# 1-Schematic_PhotoMag.net
KiCad netlist of a schematic drawn in EasyEDA
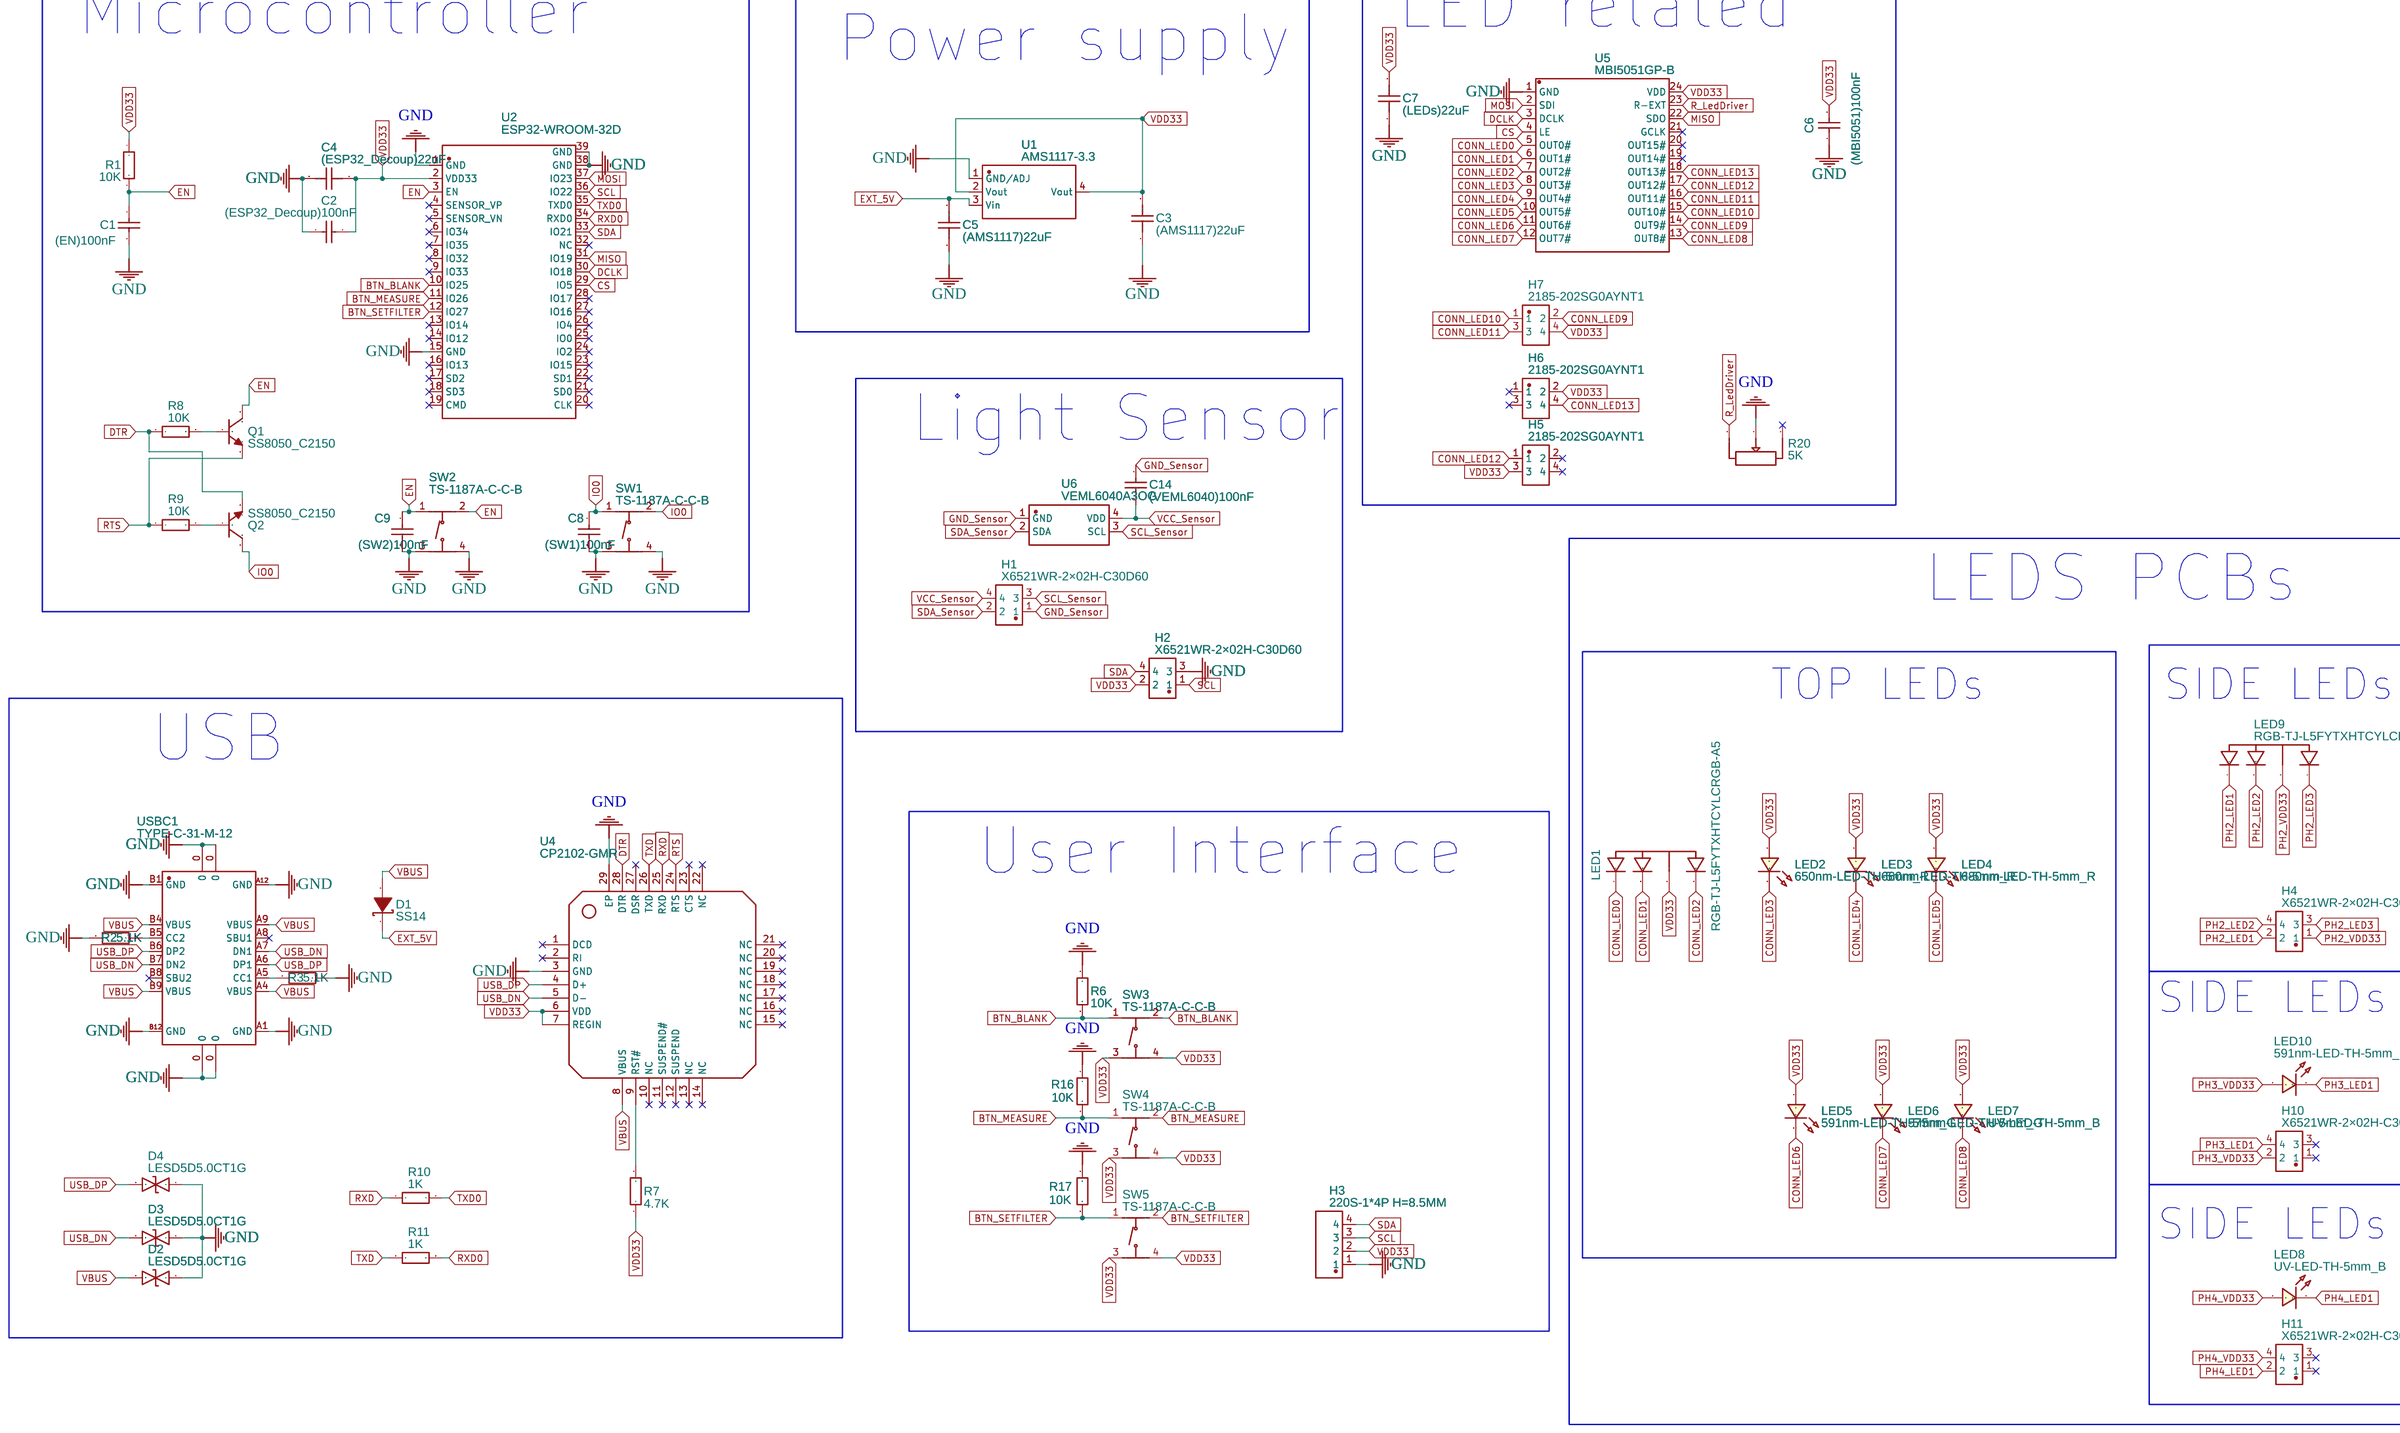
[diagram p0: schematic sheet]

(export (version "E")
  (design (tool "Eeschema 10.0.6"))
  (components
    (comp (ref "C1")
      (value "(EN)100nF")
      (fields
        (field (name "BOM_Manufacturer Part") "CL31B104KBCNNNC")
        (field (name "BOM_Supplier Part") "C24497")
      )
      (libsource (lib "") (part "CL31B104KBCNNNC_2"))
    )
    (comp (ref "C2")
      (value "(ESP32_Decoup)100nF")
      (fields
        (field (name "BOM_Manufacturer Part") "CL31B104KBCNNNC")
        (field (name "BOM_Supplier Part") "C24497")
      )
      (libsource (lib "") (part "CL31B104KBCNNNC_3"))
    )
    (comp (ref "C3")
      (value "(AMS1117)22uF")
      (fields
        (field (name "BOM_Manufacturer Part") "CL21A226MAQNNNE")
        (field (name "BOM_Supplier Part") "C45783")
      )
      (libsource (lib "") (part "CL21A226MAQNNNE"))
    )
    (comp (ref "C4")
      (value "(ESP32_Decoup)22uF")
      (fields
        (field (name "BOM_Manufacturer Part") "CL21A226MAQNNNE")
        (field (name "BOM_Supplier Part") "C45783")
      )
      (libsource (lib "") (part "CL21A226MAQNNNE_1"))
    )
    (comp (ref "C5")
      (value "(AMS1117)22uF")
      (fields
        (field (name "BOM_Manufacturer Part") "CL21A226MAQNNNE")
        (field (name "BOM_Supplier Part") "C45783")
      )
      (libsource (lib "") (part "CL21A226MAQNNNE"))
    )
    (comp (ref "C6")
      (value "(MBI5051)100nF")
      (fields
        (field (name "BOM_Manufacturer Part") "CL31B104KBCNNNC")
        (field (name "BOM_Supplier Part") "C24497")
      )
      (libsource (lib "") (part "CL31B104KBCNNNC_1"))
    )
    (comp (ref "C7")
      (value "(LEDs)22uF")
      (fields
        (field (name "BOM_Manufacturer Part") "CL21A226MAQNNNE")
        (field (name "BOM_Supplier Part") "C45783")
      )
      (libsource (lib "") (part "CL21A226MAQNNNE"))
    )
    (comp (ref "C8")
      (value "(SW1)100nF")
      (fields
        (field (name "BOM_Manufacturer Part") "CL31B104KBCNNNC")
        (field (name "BOM_Supplier Part") "C24497")
      )
      (libsource (lib "") (part "CL31B104KBCNNNC"))
    )
    (comp (ref "C9")
      (value "(SW2)100nF")
      (fields
        (field (name "BOM_Manufacturer Part") "CL31B104KBCNNNC")
        (field (name "BOM_Supplier Part") "C24497")
      )
      (libsource (lib "") (part "CL31B104KBCNNNC"))
    )
    (comp (ref "C14")
      (value "(VEML6040)100nF")
      (fields
        (field (name "BOM_Manufacturer Part") "CL31B104KBCNNNC")
        (field (name "BOM_Supplier Part") "C24497")
      )
      (libsource (lib "") (part "CL31B104KBCNNNC_4"))
    )
    (comp (ref "D1")
      (value "SS14")
      (fields (field (name "BOM_Supplier Part") "C2480"))
      (libsource (lib "") (part "SS14"))
    )
    (comp (ref "D2")
      (value "LESD5D5.0CT1G")
      (fields (field (name "BOM_Supplier Part") "C383211"))
      (libsource (lib "") (part "LESD5D5.0CT1G"))
    )
    (comp (ref "D3")
      (value "LESD5D5.0CT1G")
      (fields (field (name "BOM_Supplier Part") "C383211"))
      (libsource (lib "") (part "LESD5D5.0CT1G"))
    )
    (comp (ref "D4")
      (value "LESD5D5.0CT1G")
      (fields (field (name "BOM_Supplier Part") "C383211"))
      (libsource (lib "") (part "LESD5D5.0CT1G"))
    )
    (comp (ref "H1")
      (value "X6521WR-2×02H-C30D60")
      (fields (field (name "BOM_Supplier Part") "C706883"))
      (libsource (lib "") (part "X6521WR-2×02H-C30D60"))
    )
    (comp (ref "H2")
      (value "X6521WR-2×02H-C30D60")
      (fields (field (name "BOM_Supplier Part") "C706883"))
      (libsource (lib "") (part "X6521WR-2×02H-C30D60"))
    )
    (comp (ref "H3")
      (value "220S-1*4P H=8.5MM")
      (fields
        (field (name "BOM_Manufacturer Part") "220S-1*4P H=8.5MM Ytype Gold-plated")
        (field (name "BOM_Supplier Part") "C124413")
      )
      (libsource (lib "") (part "220S-1*4P H=8.5MM"))
    )
    (comp (ref "H4")
      (value "X6521WR-2×02H-C30D60")
      (fields (field (name "BOM_Supplier Part") "C706883"))
      (libsource (lib "") (part "X6521WR-2×02H-C30D60"))
    )
    (comp (ref "H5")
      (value "2185-202SG0AYNT1")
      (fields (field (name "BOM_Supplier Part") "C721791"))
      (libsource (lib "") (part "2185-202SG0AYNT1"))
    )
    (comp (ref "H6")
      (value "2185-202SG0AYNT1")
      (fields (field (name "BOM_Supplier Part") "C721791"))
      (libsource (lib "") (part "2185-202SG0AYNT1"))
    )
    (comp (ref "H7")
      (value "2185-202SG0AYNT1")
      (fields (field (name "BOM_Supplier Part") "C721791"))
      (libsource (lib "") (part "2185-202SG0AYNT1"))
    )
    (comp (ref "H10")
      (value "X6521WR-2×02H-C30D60")
      (fields (field (name "BOM_Supplier Part") "C706883"))
      (libsource (lib "") (part "X6521WR-2×02H-C30D60"))
    )
    (comp (ref "H11")
      (value "X6521WR-2×02H-C30D60")
      (fields (field (name "BOM_Supplier Part") "C706883"))
      (libsource (lib "") (part "X6521WR-2×02H-C30D60"))
    )
    (comp (ref "LED1")
      (value "RGB-TJ-L5FYTXHTCYLCRGB-A5")
      (fields
        (field (name "BOM_Manufacturer Part") "TJ-L5FYTXHTCYLCRGB-A5")
        (field (name "BOM_Supplier Part") "C330749")
      )
      (libsource (lib "") (part "TJ-L5FYTXHTCYLCRGB-A5"))
    )
    (comp (ref "LED2")
      (value "650nm-LED-TH-5mm_R")
      (fields
        (field (name "BOM_Manufacturer Part") "333-2SURD/S530-A3")
        (field (name "BOM_Supplier Part") "C87271")
      )
      (libsource (lib "") (part "LED-TH-5mm_R_1"))
    )
    (comp (ref "LED3")
      (value "660nm-LED-TH-5mm_R")
      (fields
        (field (name "BOM_Manufacturer Part") "333-2SURD/S530-A3")
        (field (name "BOM_Supplier Part") "C87271")
      )
      (libsource (lib "") (part "LED-TH-5mm_R_1"))
    )
    (comp (ref "LED4")
      (value "680nm-LED-TH-5mm_R")
      (fields
        (field (name "BOM_Manufacturer Part") "333-2SURD/S530-A3")
        (field (name "BOM_Supplier Part") "C87271")
      )
      (libsource (lib "") (part "LED-TH-5mm_R_1"))
    )
    (comp (ref "LED5")
      (value "591nm-LED-TH-5mm_G")
      (fields
        (field (name "BOM_Manufacturer Part") "333-2SYGD/S530-E2")
        (field (name "BOM_Supplier Part") "C88163")
      )
      (libsource (lib "") (part "LED-TH-5mm_G"))
    )
    (comp (ref "LED6")
      (value "575nm-LED-TH-5mm_G")
      (fields
        (field (name "BOM_Manufacturer Part") "333-2SYGD/S530-E2")
        (field (name "BOM_Supplier Part") "C88163")
      )
      (libsource (lib "") (part "LED-TH-5mm_G"))
    )
    (comp (ref "LED7") (value "UV-LED-TH-5mm_B") (libsource (lib "") (part "LED-TH-5mm_B_1")))
    (comp (ref "LED8") (value "UV-LED-TH-5mm_B") (libsource (lib "") (part "LED-TH-5mm_B")))
    (comp (ref "LED9")
      (value "RGB-TJ-L5FYTXHTCYLCRGB-A5")
      (fields
        (field (name "BOM_Manufacturer Part") "TJ-L5FYTXHTCYLCRGB-A5")
        (field (name "BOM_Supplier Part") "C330749")
      )
      (libsource (lib "") (part "TJ-L5FYTXHTCYLCRGB-A5"))
    )
    (comp (ref "LED10")
      (value "591nm-LED-TH-5mm_R")
      (fields
        (field (name "BOM_Manufacturer Part") "333-2SURD/S530-A3")
        (field (name "BOM_Supplier Part") "C87271")
      )
      (libsource (lib "") (part "LED-TH-5mm_R"))
    )
    (comp (ref "Q1")
      (value "SS8050_C2150")
      (fields (field (name "BOM_Manufacturer Part") "SS8050") (field (name "BOM_Supplier Part") "C2150"))
      (libsource (lib "") (part "SS8050_C2150_1"))
    )
    (comp (ref "Q2")
      (value "SS8050_C2150")
      (fields (field (name "BOM_Manufacturer Part") "SS8050") (field (name "BOM_Supplier Part") "C2150"))
      (libsource (lib "") (part "SS8050_C2150"))
    )
    (comp (ref "R1")
      (value "10K")
      (fields
        (field (name "BOM_Manufacturer Part") "0805W8F1002T5E")
        (field (name "BOM_Supplier Part") "C17414")
      )
      (libsource (lib "") (part "0805W8F1002T5E"))
    )
    (comp (ref "R2")
      (value "5.1K")
      (fields
        (field (name "BOM_Manufacturer Part") "0805W8F5101T5E")
        (field (name "BOM_Supplier Part") "C27834")
      )
      (libsource (lib "") (part "0805W8F5101T5E"))
    )
    (comp (ref "R3")
      (value "5.1K")
      (fields
        (field (name "BOM_Manufacturer Part") "0805W8F5101T5E")
        (field (name "BOM_Supplier Part") "C27834")
      )
      (libsource (lib "") (part "0805W8F5101T5E"))
    )
    (comp (ref "R6")
      (value "10K")
      (fields
        (field (name "BOM_Manufacturer Part") "0805W8F1002T5E")
        (field (name "BOM_Supplier Part") "C17414")
      )
      (libsource (lib "") (part "0805W8F1002T5E"))
    )
    (comp (ref "R7")
      (value "4.7K")
      (fields
        (field (name "BOM_Manufacturer Part") "0805W8F4701T5E")
        (field (name "BOM_Supplier Part") "C17673")
      )
      (libsource (lib "") (part "0805W8F4701T5E"))
    )
    (comp (ref "R8")
      (value "10K")
      (fields
        (field (name "BOM_Manufacturer Part") "0805W8F1002T5E")
        (field (name "BOM_Supplier Part") "C17414")
      )
      (libsource (lib "") (part "0805W8F1002T5E_1"))
    )
    (comp (ref "R9")
      (value "10K")
      (fields
        (field (name "BOM_Manufacturer Part") "0805W8F1002T5E")
        (field (name "BOM_Supplier Part") "C17414")
      )
      (libsource (lib "") (part "0805W8F1002T5E_1"))
    )
    (comp (ref "R10")
      (value "1K")
      (fields
        (field (name "BOM_Manufacturer Part") "0603WAF1001T5E")
        (field (name "BOM_Supplier Part") "C21190")
      )
      (libsource (lib "") (part "0603WAF1001T5E"))
    )
    (comp (ref "R11")
      (value "1K")
      (fields
        (field (name "BOM_Manufacturer Part") "0603WAF1001T5E")
        (field (name "BOM_Supplier Part") "C21190")
      )
      (libsource (lib "") (part "0603WAF1001T5E"))
    )
    (comp (ref "R16")
      (value "10K")
      (fields
        (field (name "BOM_Manufacturer Part") "0805W8F1002T5E")
        (field (name "BOM_Supplier Part") "C17414")
      )
      (libsource (lib "") (part "0805W8F1002T5E"))
    )
    (comp (ref "R17")
      (value "10K")
      (fields
        (field (name "BOM_Manufacturer Part") "0805W8F1002T5E")
        (field (name "BOM_Supplier Part") "C17414")
      )
      (libsource (lib "") (part "0805W8F1002T5E"))
    )
    (comp (ref "R20")
      (value "5K")
      (fields
        (field (name "BOM_Manufacturer Part") "3266W-1-502")
        (field (name "BOM_Supplier Part") "C118905")
      )
      (libsource (lib "") (part "3266W-1-502"))
    )
    (comp (ref "SW1")
      (value "TS-1187A-C-C-B")
      (fields (field (name "BOM_Supplier Part") "C318889"))
      (libsource (lib "") (part "TS-1187A-C-C-B"))
    )
    (comp (ref "SW2")
      (value "TS-1187A-C-C-B")
      (fields (field (name "BOM_Supplier Part") "C318889"))
      (libsource (lib "") (part "TS-1187A-C-C-B"))
    )
    (comp (ref "SW3")
      (value "TS-1187A-C-C-B")
      (fields (field (name "BOM_Supplier Part") "C318889"))
      (libsource (lib "") (part "TS-1187A-C-C-B"))
    )
    (comp (ref "SW4")
      (value "TS-1187A-C-C-B")
      (fields (field (name "BOM_Supplier Part") "C318889"))
      (libsource (lib "") (part "TS-1187A-C-C-B"))
    )
    (comp (ref "SW5")
      (value "TS-1187A-C-C-B")
      (fields (field (name "BOM_Supplier Part") "C318889"))
      (libsource (lib "") (part "TS-1187A-C-C-B"))
    )
    (comp (ref "U1")
      (value "AMS1117-3.3")
      (fields (field (name "BOM_Supplier Part") "C6186"))
      (libsource (lib "") (part "AMS1117-3.3"))
    )
    (comp (ref "U2")
      (value "ESP32-WROOM-32D")
      (fields (field (name "BOM_Supplier Part") "C473012"))
      (libsource (lib "") (part "ESP32-WROOM-32D"))
    )
    (comp (ref "U4")
      (value "CP2102-GMR")
      (fields (field (name "BOM_Supplier Part") "C6568"))
      (libsource (lib "") (part "CP2102-GMR"))
    )
    (comp (ref "U5")
      (value "MBI5051GP-B")
      (fields (field (name "BOM_Supplier Part") "C261126"))
      (libsource (lib "") (part "MBI5051GP-B"))
    )
    (comp (ref "U6")
      (value "VEML6040A3OG")
      (fields (field (name "BOM_Supplier Part") "C78465"))
      (libsource (lib "") (part "VEML6040A3OG"))
    )
    (comp (ref "USBC1")
      (value "TYPE-C-31-M-12")
      (fields (field (name "BOM_Supplier Part") "C165948"))
      (libsource (lib "") (part "TYPE-C-31-M-12"))
    )
  )
  (nets
    (net (code "1") (name "BTN_BLANK") (class "Default")
      (node (ref "R6") (pin "2") (pinfunction "2_2") (pintype "input"))
      (node (ref "SW3") (pin "1") (pinfunction "A_1") (pintype "unspecified"))
      (node (ref "SW3") (pin "2") (pinfunction "B_2") (pintype "unspecified"))
      (node (ref "U2") (pin "10") (pinfunction "IO25_10") (pintype "unspecified"))
    )
    (net (code "2") (name "BTN_MEASURE") (class "Default")
      (node (ref "R16") (pin "2") (pinfunction "2_2") (pintype "input"))
      (node (ref "SW4") (pin "1") (pinfunction "A_1") (pintype "unspecified"))
      (node (ref "SW4") (pin "2") (pinfunction "B_2") (pintype "unspecified"))
      (node (ref "U2") (pin "11") (pinfunction "IO26_11") (pintype "unspecified"))
    )
    (net (code "3") (name "BTN_SETFILTER") (class "Default")
      (node (ref "R17") (pin "2") (pinfunction "2_2") (pintype "input"))
      (node (ref "SW5") (pin "1") (pinfunction "A_1") (pintype "unspecified"))
      (node (ref "SW5") (pin "2") (pinfunction "B_2") (pintype "unspecified"))
      (node (ref "U2") (pin "12") (pinfunction "IO27_12") (pintype "unspecified"))
    )
    (net (code "4") (name "CONN_LED0") (class "Default")
      (node (ref "LED1") (pin "4") (pinfunction "4_4") (pintype "unspecified"))
      (node (ref "U5") (pin "5") (pinfunction "OUT0#_5") (pintype "unspecified"))
    )
    (net (code "5") (name "CONN_LED1") (class "Default")
      (node (ref "LED1") (pin "3") (pinfunction "3_3") (pintype "unspecified"))
      (node (ref "U5") (pin "6") (pinfunction "OUT1#_6") (pintype "unspecified"))
    )
    (net (code "6") (name "CONN_LED2") (class "Default")
      (node (ref "LED1") (pin "1") (pinfunction "1_1") (pintype "unspecified"))
      (node (ref "U5") (pin "7") (pinfunction "OUT2#_7") (pintype "unspecified"))
    )
    (net (code "7") (name "CONN_LED3") (class "Default")
      (node (ref "LED2") (pin "2") (pinfunction "2_2") (pintype "unspecified"))
      (node (ref "U5") (pin "8") (pinfunction "OUT3#_8") (pintype "unspecified"))
    )
    (net (code "8") (name "CONN_LED4") (class "Default")
      (node (ref "LED3") (pin "2") (pinfunction "2_2") (pintype "unspecified"))
      (node (ref "U5") (pin "9") (pinfunction "OUT4#_9") (pintype "unspecified"))
    )
    (net (code "9") (name "CONN_LED5") (class "Default")
      (node (ref "LED4") (pin "2") (pinfunction "2_2") (pintype "unspecified"))
      (node (ref "U5") (pin "10") (pinfunction "OUT5#_10") (pintype "unspecified"))
    )
    (net (code "10") (name "CONN_LED6") (class "Default")
      (node (ref "LED5") (pin "2") (pinfunction "2_2") (pintype "unspecified"))
      (node (ref "U5") (pin "11") (pinfunction "OUT6#_11") (pintype "unspecified"))
    )
    (net (code "11") (name "CONN_LED7") (class "Default")
      (node (ref "LED6") (pin "2") (pinfunction "2_2") (pintype "unspecified"))
      (node (ref "U5") (pin "12") (pinfunction "OUT7#_12") (pintype "unspecified"))
    )
    (net (code "12") (name "CONN_LED8") (class "Default")
      (node (ref "LED7") (pin "2") (pinfunction "2_2") (pintype "unspecified"))
      (node (ref "U5") (pin "13") (pinfunction "OUT8#_13") (pintype "unspecified"))
    )
    (net (code "13") (name "CONN_LED9") (class "Default")
      (node (ref "H7") (pin "2") (pinfunction "2_2") (pintype "unspecified"))
      (node (ref "U5") (pin "14") (pinfunction "OUT9#_14") (pintype "unspecified"))
    )
    (net (code "14") (name "CONN_LED10") (class "Default")
      (node (ref "H7") (pin "1") (pinfunction "1_1") (pintype "unspecified"))
      (node (ref "U5") (pin "15") (pinfunction "OUT10#_15") (pintype "unspecified"))
    )
    (net (code "15") (name "CONN_LED11") (class "Default")
      (node (ref "H7") (pin "3") (pinfunction "3_3") (pintype "unspecified"))
      (node (ref "U5") (pin "16") (pinfunction "OUT11#_16") (pintype "unspecified"))
    )
    (net (code "16") (name "CONN_LED12") (class "Default")
      (node (ref "H5") (pin "1") (pinfunction "1_1") (pintype "unspecified"))
      (node (ref "U5") (pin "17") (pinfunction "OUT12#_17") (pintype "unspecified"))
    )
    (net (code "17") (name "CONN_LED13") (class "Default")
      (node (ref "H6") (pin "4") (pinfunction "4_4") (pintype "unspecified"))
      (node (ref "U5") (pin "18") (pinfunction "OUT13#_18") (pintype "unspecified"))
    )
    (net (code "18") (name "CS") (class "Default")
      (node (ref "U2") (pin "29") (pinfunction "IO5_29") (pintype "unspecified"))
      (node (ref "U5") (pin "4") (pinfunction "LE_4") (pintype "unspecified"))
    )
    (net (code "19") (name "DCLK") (class "Default")
      (node (ref "U2") (pin "30") (pinfunction "IO18_30") (pintype "unspecified"))
      (node (ref "U5") (pin "3") (pinfunction "DCLK_3") (pintype "unspecified"))
    )
    (net (code "20") (name "DTR") (class "Default")
      (node (ref "Q2") (pin "2") (pinfunction "E_2") (pintype "unspecified"))
      (node (ref "R8") (pin "1") (pinfunction "1_1") (pintype "input"))
      (node (ref "U4") (pin "28") (pinfunction "DTR_28") (pintype "unspecified"))
    )
    (net (code "21") (name "EN") (class "Default")
      (node (ref "C1") (pin "1") (pinfunction "1_1") (pintype "input"))
      (node (ref "C9") (pin "1") (pinfunction "1_1") (pintype "input"))
      (node (ref "Q1") (pin "3") (pinfunction "C_3") (pintype "unspecified"))
      (node (ref "R1") (pin "2") (pinfunction "2_2") (pintype "input"))
      (node (ref "SW2") (pin "1") (pinfunction "A_1") (pintype "unspecified"))
      (node (ref "SW2") (pin "2") (pinfunction "B_2") (pintype "unspecified"))
      (node (ref "U2") (pin "3") (pinfunction "EN_3") (pintype "unspecified"))
    )
    (net (code "22") (name "EXT_5V") (class "Default")
      (node (ref "C5") (pin "2") (pinfunction "2_2") (pintype "unspecified"))
      (node (ref "D1") (pin "1") (pinfunction "K_1") (pintype "unspecified"))
      (node (ref "U1") (pin "3") (pinfunction "Vin_3") (pintype "unspecified"))
    )
    (net (code "23") (name "GND") (class "Default")
      (node (ref "C1") (pin "2") (pinfunction "2_2") (pintype "input"))
      (node (ref "C2") (pin "1") (pinfunction "1_1") (pintype "input"))
      (node (ref "C3") (pin "1") (pinfunction "1_1") (pintype "unspecified"))
      (node (ref "C4") (pin "2") (pinfunction "2_2") (pintype "unspecified"))
      (node (ref "C5") (pin "1") (pinfunction "1_1") (pintype "unspecified"))
      (node (ref "C6") (pin "1") (pinfunction "1_1") (pintype "input"))
      (node (ref "C7") (pin "1") (pinfunction "1_1") (pintype "unspecified"))
      (node (ref "C8") (pin "2") (pinfunction "2_2") (pintype "input"))
      (node (ref "C9") (pin "2") (pinfunction "2_2") (pintype "input"))
      (node (ref "D2") (pin "1") (pinfunction "1_1") (pintype "unspecified"))
      (node (ref "D3") (pin "1") (pinfunction "1_1") (pintype "unspecified"))
      (node (ref "D4") (pin "1") (pinfunction "1_1") (pintype "unspecified"))
      (node (ref "H2") (pin "3") (pinfunction "3_3") (pintype "unspecified"))
      (node (ref "H3") (pin "1") (pinfunction "1_1") (pintype "unspecified"))
      (node (ref "R16") (pin "1") (pinfunction "1_1") (pintype "input"))
      (node (ref "R17") (pin "1") (pinfunction "1_1") (pintype "input"))
      (node (ref "R2") (pin "2") (pinfunction "2_2") (pintype "input"))
      (node (ref "R20") (pin "2") (pinfunction "2_2") (pintype "unspecified"))
      (node (ref "R3") (pin "1") (pinfunction "1_1") (pintype "input"))
      (node (ref "R6") (pin "1") (pinfunction "1_1") (pintype "input"))
      (node (ref "SW1") (pin "3") (pinfunction "C_3") (pintype "unspecified"))
      (node (ref "SW1") (pin "4") (pinfunction "D_4") (pintype "unspecified"))
      (node (ref "SW2") (pin "3") (pinfunction "C_3") (pintype "unspecified"))
      (node (ref "SW2") (pin "4") (pinfunction "D_4") (pintype "unspecified"))
      (node (ref "U1") (pin "1") (pinfunction "GND/ADJ_1") (pintype "unspecified"))
      (node (ref "U2") (pin "1") (pinfunction "GND_1") (pintype "unspecified"))
      (node (ref "U2") (pin "15") (pinfunction "GND_15") (pintype "unspecified"))
      (node (ref "U2") (pin "38") (pinfunction "GND_38") (pintype "unspecified"))
      (node (ref "U2") (pin "39") (pinfunction "GND_39") (pintype "unspecified"))
      (node (ref "U4") (pin "29") (pinfunction "EP_29") (pintype "unspecified"))
      (node (ref "U4") (pin "3") (pinfunction "GND_3") (pintype "unspecified"))
      (node (ref "U5") (pin "1") (pinfunction "GND_1") (pintype "unspecified"))
      (node (ref "USBC1") (pin "0") (pinfunction "0_0") (pintype "unspecified"))
      (node (ref "USBC1") (pin "A1") (pinfunction "GND_A1") (pintype "unspecified"))
      (node (ref "USBC1") (pin "A12") (pinfunction "GND_A12") (pintype "unspecified"))
      (node (ref "USBC1") (pin "B1") (pinfunction "GND_B1") (pintype "unspecified"))
      (node (ref "USBC1") (pin "B12") (pinfunction "GND_B12") (pintype "unspecified"))
    )
    (net (code "24") (name "GND_Sensor") (class "Default")
      (node (ref "C14") (pin "2") (pinfunction "2_2") (pintype "input"))
      (node (ref "H1") (pin "1") (pinfunction "1_1") (pintype "unspecified"))
      (node (ref "U6") (pin "1") (pinfunction "GND_1") (pintype "unspecified"))
    )
    (net (code "25") (name "IO0") (class "Default")
      (node (ref "C8") (pin "1") (pinfunction "1_1") (pintype "input"))
      (node (ref "Q2") (pin "3") (pinfunction "C_3") (pintype "unspecified"))
      (node (ref "SW1") (pin "1") (pinfunction "A_1") (pintype "unspecified"))
      (node (ref "SW1") (pin "2") (pinfunction "B_2") (pintype "unspecified"))
    )
    (net (code "26") (name "MISO") (class "Default")
      (node (ref "U2") (pin "31") (pinfunction "IO19_31") (pintype "unspecified"))
      (node (ref "U5") (pin "22") (pinfunction "SDO_22") (pintype "unspecified"))
    )
    (net (code "27") (name "MOSI") (class "Default")
      (node (ref "U2") (pin "37") (pinfunction "IO23_37") (pintype "unspecified"))
      (node (ref "U5") (pin "2") (pinfunction "SDI_2") (pintype "unspecified"))
    )
    (net (code "28") (name "Net-(Q1-B)") (class "Default")
      (node (ref "Q1") (pin "1") (pinfunction "B_1") (pintype "unspecified"))
      (node (ref "R8") (pin "2") (pinfunction "2_2") (pintype "input"))
    )
    (net (code "29") (name "Net-(Q2-B)") (class "Default")
      (node (ref "Q2") (pin "1") (pinfunction "B_1") (pintype "unspecified"))
      (node (ref "R9") (pin "2") (pinfunction "2_2") (pintype "input"))
    )
    (net (code "30") (name "Net-(U4-RST#)") (class "Default")
      (node (ref "R7") (pin "2") (pinfunction "2_2") (pintype "input"))
      (node (ref "U4") (pin "9") (pinfunction "RST#_9") (pintype "unspecified"))
    )
    (net (code "31") (name "Net-(USBC1-CC1)") (class "Default")
      (node (ref "R3") (pin "2") (pinfunction "2_2") (pintype "input"))
      (node (ref "USBC1") (pin "A5") (pinfunction "CC1_A5") (pintype "unspecified"))
    )
    (net (code "32") (name "Net-(USBC1-CC2)") (class "Default")
      (node (ref "R2") (pin "1") (pinfunction "1_1") (pintype "input"))
      (node (ref "USBC1") (pin "B5") (pinfunction "CC2_B5") (pintype "unspecified"))
    )
    (net (code "33") (name "PH2_LED1") (class "Default")
      (node (ref "H4") (pin "2") (pinfunction "2_2") (pintype "unspecified"))
      (node (ref "LED9") (pin "4") (pinfunction "4_4") (pintype "unspecified"))
    )
    (net (code "34") (name "PH2_LED2") (class "Default")
      (node (ref "H4") (pin "4") (pinfunction "4_4") (pintype "unspecified"))
      (node (ref "LED9") (pin "3") (pinfunction "3_3") (pintype "unspecified"))
    )
    (net (code "35") (name "PH2_LED3") (class "Default")
      (node (ref "H4") (pin "3") (pinfunction "3_3") (pintype "unspecified"))
      (node (ref "LED9") (pin "1") (pinfunction "1_1") (pintype "unspecified"))
    )
    (net (code "36") (name "PH2_VDD33") (class "Default")
      (node (ref "H4") (pin "1") (pinfunction "1_1") (pintype "unspecified"))
      (node (ref "LED9") (pin "2") (pinfunction "+_2") (pintype "unspecified"))
    )
    (net (code "37") (name "PH3_LED1") (class "Default")
      (node (ref "H10") (pin "4") (pinfunction "4_4") (pintype "unspecified"))
      (node (ref "LED10") (pin "2") (pinfunction "2_2") (pintype "unspecified"))
    )
    (net (code "38") (name "PH3_VDD33") (class "Default")
      (node (ref "H10") (pin "2") (pinfunction "2_2") (pintype "unspecified"))
      (node (ref "LED10") (pin "1") (pinfunction "1_1") (pintype "unspecified"))
    )
    (net (code "39") (name "PH4_LED1") (class "Default")
      (node (ref "H11") (pin "2") (pinfunction "2_2") (pintype "unspecified"))
      (node (ref "LED8") (pin "2") (pinfunction "2_2") (pintype "unspecified"))
    )
    (net (code "40") (name "PH4_VDD33") (class "Default")
      (node (ref "H11") (pin "4") (pinfunction "4_4") (pintype "unspecified"))
      (node (ref "LED8") (pin "1") (pinfunction "1_1") (pintype "unspecified"))
    )
    (net (code "41") (name "RTS") (class "Default")
      (node (ref "Q1") (pin "2") (pinfunction "E_2") (pintype "unspecified"))
      (node (ref "R9") (pin "1") (pinfunction "1_1") (pintype "input"))
      (node (ref "U4") (pin "24") (pinfunction "RTS_24") (pintype "unspecified"))
    )
    (net (code "42") (name "RXD") (class "Default")
      (node (ref "R10") (pin "1") (pinfunction "1_1") (pintype "input"))
      (node (ref "U4") (pin "25") (pinfunction "RXD_25") (pintype "unspecified"))
    )
    (net (code "43") (name "RXD0") (class "Default")
      (node (ref "R11") (pin "2") (pinfunction "2_2") (pintype "input"))
      (node (ref "U2") (pin "34") (pinfunction "RXD0_34") (pintype "unspecified"))
    )
    (net (code "44") (name "R_LedDriver") (class "Default")
      (node (ref "R20") (pin "3") (pinfunction "3_3") (pintype "unspecified"))
      (node (ref "U5") (pin "23") (pinfunction "R-EXT_23") (pintype "unspecified"))
    )
    (net (code "45") (name "SCL") (class "Default")
      (node (ref "H2") (pin "1") (pinfunction "1_1") (pintype "unspecified"))
      (node (ref "H3") (pin "3") (pinfunction "3_3") (pintype "unspecified"))
      (node (ref "U2") (pin "36") (pinfunction "IO22_36") (pintype "unspecified"))
    )
    (net (code "46") (name "SCL_Sensor") (class "Default")
      (node (ref "H1") (pin "3") (pinfunction "3_3") (pintype "unspecified"))
      (node (ref "U6") (pin "3") (pinfunction "SCL_3") (pintype "unspecified"))
    )
    (net (code "47") (name "SDA") (class "Default")
      (node (ref "H2") (pin "4") (pinfunction "4_4") (pintype "unspecified"))
      (node (ref "H3") (pin "4") (pinfunction "4_4") (pintype "unspecified"))
      (node (ref "U2") (pin "33") (pinfunction "IO21_33") (pintype "unspecified"))
    )
    (net (code "48") (name "SDA_Sensor") (class "Default")
      (node (ref "H1") (pin "2") (pinfunction "2_2") (pintype "unspecified"))
      (node (ref "U6") (pin "2") (pinfunction "SDA_2") (pintype "unspecified"))
    )
    (net (code "49") (name "TXD") (class "Default")
      (node (ref "R11") (pin "1") (pinfunction "1_1") (pintype "input"))
      (node (ref "U4") (pin "26") (pinfunction "TXD_26") (pintype "unspecified"))
    )
    (net (code "50") (name "TXD0") (class "Default")
      (node (ref "R10") (pin "2") (pinfunction "2_2") (pintype "input"))
      (node (ref "U2") (pin "35") (pinfunction "TXD0_35") (pintype "unspecified"))
    )
    (net (code "51") (name "USB_DN") (class "Default")
      (node (ref "D3") (pin "2") (pinfunction "2_2") (pintype "unspecified"))
      (node (ref "U4") (pin "5") (pinfunction "D-_5") (pintype "unspecified"))
      (node (ref "USBC1") (pin "A7") (pinfunction "DN1_A7") (pintype "unspecified"))
      (node (ref "USBC1") (pin "B7") (pinfunction "DN2_B7") (pintype "unspecified"))
    )
    (net (code "52") (name "USB_DP") (class "Default")
      (node (ref "D4") (pin "2") (pinfunction "2_2") (pintype "unspecified"))
      (node (ref "U4") (pin "4") (pinfunction "D+_4") (pintype "unspecified"))
      (node (ref "USBC1") (pin "A6") (pinfunction "DP1_A6") (pintype "unspecified"))
      (node (ref "USBC1") (pin "B6") (pinfunction "DP2_B6") (pintype "unspecified"))
    )
    (net (code "53") (name "VBUS") (class "Default")
      (node (ref "D1") (pin "2") (pinfunction "A_2") (pintype "unspecified"))
      (node (ref "D2") (pin "2") (pinfunction "2_2") (pintype "unspecified"))
      (node (ref "U4") (pin "8") (pinfunction "VBUS_8") (pintype "unspecified"))
      (node (ref "USBC1") (pin "A4") (pinfunction "VBUS_A4") (pintype "unspecified"))
      (node (ref "USBC1") (pin "A9") (pinfunction "VBUS_A9") (pintype "unspecified"))
      (node (ref "USBC1") (pin "B4") (pinfunction "VBUS_B4") (pintype "unspecified"))
      (node (ref "USBC1") (pin "B9") (pinfunction "VBUS_B9") (pintype "unspecified"))
    )
    (net (code "54") (name "VCC_Sensor") (class "Default")
      (node (ref "C14") (pin "1") (pinfunction "1_1") (pintype "input"))
      (node (ref "H1") (pin "4") (pinfunction "4_4") (pintype "unspecified"))
      (node (ref "U6") (pin "4") (pinfunction "VDD_4") (pintype "unspecified"))
    )
    (net (code "55") (name "VDD33") (class "Default")
      (node (ref "C2") (pin "2") (pinfunction "2_2") (pintype "input"))
      (node (ref "C3") (pin "2") (pinfunction "2_2") (pintype "unspecified"))
      (node (ref "C4") (pin "1") (pinfunction "1_1") (pintype "unspecified"))
      (node (ref "C6") (pin "2") (pinfunction "2_2") (pintype "input"))
      (node (ref "C7") (pin "2") (pinfunction "2_2") (pintype "unspecified"))
      (node (ref "H2") (pin "2") (pinfunction "2_2") (pintype "unspecified"))
      (node (ref "H3") (pin "2") (pinfunction "2_2") (pintype "unspecified"))
      (node (ref "H5") (pin "3") (pinfunction "3_3") (pintype "unspecified"))
      (node (ref "H6") (pin "2") (pinfunction "2_2") (pintype "unspecified"))
      (node (ref "H7") (pin "4") (pinfunction "4_4") (pintype "unspecified"))
      (node (ref "LED1") (pin "2") (pinfunction "+_2") (pintype "unspecified"))
      (node (ref "LED2") (pin "1") (pinfunction "1_1") (pintype "unspecified"))
      (node (ref "LED3") (pin "1") (pinfunction "1_1") (pintype "unspecified"))
      (node (ref "LED4") (pin "1") (pinfunction "1_1") (pintype "unspecified"))
      (node (ref "LED5") (pin "1") (pinfunction "1_1") (pintype "unspecified"))
      (node (ref "LED6") (pin "1") (pinfunction "1_1") (pintype "unspecified"))
      (node (ref "LED7") (pin "1") (pinfunction "1_1") (pintype "unspecified"))
      (node (ref "R1") (pin "1") (pinfunction "1_1") (pintype "input"))
      (node (ref "R7") (pin "1") (pinfunction "1_1") (pintype "input"))
      (node (ref "SW3") (pin "3") (pinfunction "C_3") (pintype "unspecified"))
      (node (ref "SW3") (pin "4") (pinfunction "D_4") (pintype "unspecified"))
      (node (ref "SW4") (pin "3") (pinfunction "C_3") (pintype "unspecified"))
      (node (ref "SW4") (pin "4") (pinfunction "D_4") (pintype "unspecified"))
      (node (ref "SW5") (pin "3") (pinfunction "C_3") (pintype "unspecified"))
      (node (ref "SW5") (pin "4") (pinfunction "D_4") (pintype "unspecified"))
      (node (ref "U1") (pin "2") (pinfunction "Vout_2") (pintype "unspecified"))
      (node (ref "U1") (pin "4") (pinfunction "Vout_4") (pintype "unspecified"))
      (node (ref "U2") (pin "2") (pinfunction "VDD33_2") (pintype "unspecified"))
      (node (ref "U4") (pin "6") (pinfunction "VDD_6") (pintype "unspecified"))
      (node (ref "U4") (pin "7") (pinfunction "REGIN_7") (pintype "unspecified"))
      (node (ref "U5") (pin "24") (pinfunction "VDD_24") (pintype "unspecified"))
    )
    (net (code "56") (name "unconnected-(H5-Pad2)") (class "Default")
      (node (ref "H5") (pin "2") (pinfunction "2_2") (pintype "unspecified+no_connect"))
    )
    (net (code "57") (name "unconnected-(H5-Pad4)") (class "Default")
      (node (ref "H5") (pin "4") (pinfunction "4_4") (pintype "unspecified+no_connect"))
    )
    (net (code "58") (name "unconnected-(H6-Pad1)") (class "Default")
      (node (ref "H6") (pin "1") (pinfunction "1_1") (pintype "unspecified+no_connect"))
    )
    (net (code "59") (name "unconnected-(H6-Pad3)") (class "Default")
      (node (ref "H6") (pin "3") (pinfunction "3_3") (pintype "unspecified+no_connect"))
    )
    (net (code "60") (name "unconnected-(H10-Pad1)") (class "Default")
      (node (ref "H10") (pin "1") (pinfunction "1_1") (pintype "unspecified+no_connect"))
    )
    (net (code "61") (name "unconnected-(H10-Pad3)") (class "Default")
      (node (ref "H10") (pin "3") (pinfunction "3_3") (pintype "unspecified+no_connect"))
    )
    (net (code "62") (name "unconnected-(H11-Pad1)") (class "Default")
      (node (ref "H11") (pin "1") (pinfunction "1_1") (pintype "unspecified+no_connect"))
    )
    (net (code "63") (name "unconnected-(H11-Pad3)") (class "Default")
      (node (ref "H11") (pin "3") (pinfunction "3_3") (pintype "unspecified+no_connect"))
    )
    (net (code "64") (name "unconnected-(R20-Pad1)") (class "Default")
      (node (ref "R20") (pin "1") (pinfunction "1_1") (pintype "unspecified+no_connect"))
    )
    (net (code "65") (name "unconnected-(U2-CLK-Pad20)") (class "Default")
      (node (ref "U2") (pin "20") (pinfunction "CLK_20") (pintype "unspecified+no_connect"))
    )
    (net (code "66") (name "unconnected-(U2-CMD-Pad19)") (class "Default")
      (node (ref "U2") (pin "19") (pinfunction "CMD_19") (pintype "unspecified+no_connect"))
    )
    (net (code "67") (name "unconnected-(U2-IO0-Pad25)") (class "Default")
      (node (ref "U2") (pin "25") (pinfunction "IO0_25") (pintype "unspecified+no_connect"))
    )
    (net (code "68") (name "unconnected-(U2-IO2-Pad24)") (class "Default")
      (node (ref "U2") (pin "24") (pinfunction "IO2_24") (pintype "unspecified+no_connect"))
    )
    (net (code "69") (name "unconnected-(U2-IO4-Pad26)") (class "Default")
      (node (ref "U2") (pin "26") (pinfunction "IO4_26") (pintype "unspecified+no_connect"))
    )
    (net (code "70") (name "unconnected-(U2-IO12-Pad14)") (class "Default")
      (node (ref "U2") (pin "14") (pinfunction "IO12_14") (pintype "unspecified+no_connect"))
    )
    (net (code "71") (name "unconnected-(U2-IO13-Pad16)") (class "Default")
      (node (ref "U2") (pin "16") (pinfunction "IO13_16") (pintype "unspecified+no_connect"))
    )
    (net (code "72") (name "unconnected-(U2-IO14-Pad13)") (class "Default")
      (node (ref "U2") (pin "13") (pinfunction "IO14_13") (pintype "unspecified+no_connect"))
    )
    (net (code "73") (name "unconnected-(U2-IO15-Pad23)") (class "Default")
      (node (ref "U2") (pin "23") (pinfunction "IO15_23") (pintype "unspecified+no_connect"))
    )
    (net (code "74") (name "unconnected-(U2-IO16-Pad27)") (class "Default")
      (node (ref "U2") (pin "27") (pinfunction "IO16_27") (pintype "unspecified+no_connect"))
    )
    (net (code "75") (name "unconnected-(U2-IO17-Pad28)") (class "Default")
      (node (ref "U2") (pin "28") (pinfunction "IO17_28") (pintype "unspecified+no_connect"))
    )
    (net (code "76") (name "unconnected-(U2-IO32-Pad8)") (class "Default")
      (node (ref "U2") (pin "8") (pinfunction "IO32_8") (pintype "unspecified+no_connect"))
    )
    (net (code "77") (name "unconnected-(U2-IO33-Pad9)") (class "Default")
      (node (ref "U2") (pin "9") (pinfunction "IO33_9") (pintype "unspecified+no_connect"))
    )
    (net (code "78") (name "unconnected-(U2-IO34-Pad6)") (class "Default")
      (node (ref "U2") (pin "6") (pinfunction "IO34_6") (pintype "unspecified+no_connect"))
    )
    (net (code "79") (name "unconnected-(U2-IO35-Pad7)") (class "Default")
      (node (ref "U2") (pin "7") (pinfunction "IO35_7") (pintype "unspecified+no_connect"))
    )
    (net (code "80") (name "unconnected-(U2-NC-Pad32)") (class "Default")
      (node (ref "U2") (pin "32") (pinfunction "NC_32") (pintype "unspecified+no_connect"))
    )
    (net (code "81") (name "unconnected-(U2-SD0-Pad21)") (class "Default")
      (node (ref "U2") (pin "21") (pinfunction "SD0_21") (pintype "unspecified+no_connect"))
    )
    (net (code "82") (name "unconnected-(U2-SD1-Pad22)") (class "Default")
      (node (ref "U2") (pin "22") (pinfunction "SD1_22") (pintype "unspecified+no_connect"))
    )
    (net (code "83") (name "unconnected-(U2-SD2-Pad17)") (class "Default")
      (node (ref "U2") (pin "17") (pinfunction "SD2_17") (pintype "unspecified+no_connect"))
    )
    (net (code "84") (name "unconnected-(U2-SD3-Pad18)") (class "Default")
      (node (ref "U2") (pin "18") (pinfunction "SD3_18") (pintype "unspecified+no_connect"))
    )
    (net (code "85") (name "unconnected-(U2-SENSOR_VN-Pad5)") (class "Default")
      (node (ref "U2") (pin "5") (pinfunction "SENSOR_VN_5") (pintype "unspecified+no_connect"))
    )
    (net (code "86") (name "unconnected-(U2-SENSOR_VP-Pad4)") (class "Default")
      (node (ref "U2") (pin "4") (pinfunction "SENSOR_VP_4") (pintype "unspecified+no_connect"))
    )
    (net (code "87") (name "unconnected-(U4-CTS-Pad23)") (class "Default")
      (node (ref "U4") (pin "23") (pinfunction "CTS_23") (pintype "unspecified+no_connect"))
    )
    (net (code "88") (name "unconnected-(U4-DCD-Pad1)") (class "Default")
      (node (ref "U4") (pin "1") (pinfunction "DCD_1") (pintype "unspecified+no_connect"))
    )
    (net (code "89") (name "unconnected-(U4-DSR-Pad27)") (class "Default")
      (node (ref "U4") (pin "27") (pinfunction "DSR_27") (pintype "unspecified+no_connect"))
    )
    (net (code "90") (name "unconnected-(U4-NC-Pad10)") (class "Default")
      (node (ref "U4") (pin "10") (pinfunction "NC_10") (pintype "unspecified+no_connect"))
    )
    (net (code "91") (name "unconnected-(U4-NC-Pad13)") (class "Default")
      (node (ref "U4") (pin "13") (pinfunction "NC_13") (pintype "unspecified+no_connect"))
    )
    (net (code "92") (name "unconnected-(U4-NC-Pad14)") (class "Default")
      (node (ref "U4") (pin "14") (pinfunction "NC_14") (pintype "unspecified+no_connect"))
    )
    (net (code "93") (name "unconnected-(U4-NC-Pad15)") (class "Default")
      (node (ref "U4") (pin "15") (pinfunction "NC_15") (pintype "unspecified+no_connect"))
    )
    (net (code "94") (name "unconnected-(U4-NC-Pad16)") (class "Default")
      (node (ref "U4") (pin "16") (pinfunction "NC_16") (pintype "unspecified+no_connect"))
    )
    (net (code "95") (name "unconnected-(U4-NC-Pad17)") (class "Default")
      (node (ref "U4") (pin "17") (pinfunction "NC_17") (pintype "unspecified+no_connect"))
    )
    (net (code "96") (name "unconnected-(U4-NC-Pad18)") (class "Default")
      (node (ref "U4") (pin "18") (pinfunction "NC_18") (pintype "unspecified+no_connect"))
    )
    (net (code "97") (name "unconnected-(U4-NC-Pad19)") (class "Default")
      (node (ref "U4") (pin "19") (pinfunction "NC_19") (pintype "unspecified+no_connect"))
    )
    (net (code "98") (name "unconnected-(U4-NC-Pad20)") (class "Default")
      (node (ref "U4") (pin "20") (pinfunction "NC_20") (pintype "unspecified+no_connect"))
    )
    (net (code "99") (name "unconnected-(U4-NC-Pad21)") (class "Default")
      (node (ref "U4") (pin "21") (pinfunction "NC_21") (pintype "unspecified+no_connect"))
    )
    (net (code "100") (name "unconnected-(U4-NC-Pad22)") (class "Default")
      (node (ref "U4") (pin "22") (pinfunction "NC_22") (pintype "unspecified+no_connect"))
    )
    (net (code "101") (name "unconnected-(U4-RI-Pad2)") (class "Default")
      (node (ref "U4") (pin "2") (pinfunction "RI_2") (pintype "unspecified+no_connect"))
    )
    (net (code "102") (name "unconnected-(U4-SUSPEND#-Pad11)") (class "Default")
      (node (ref "U4") (pin "11") (pinfunction "SUSPEND#_11") (pintype "unspecified+no_connect"))
    )
    (net (code "103") (name "unconnected-(U4-SUSPEND-Pad12)") (class "Default")
      (node (ref "U4") (pin "12") (pinfunction "SUSPEND_12") (pintype "unspecified+no_connect"))
    )
    (net (code "104") (name "unconnected-(U5-GCLK-Pad21)") (class "Default")
      (node (ref "U5") (pin "21") (pinfunction "GCLK_21") (pintype "unspecified+no_connect"))
    )
    (net (code "105") (name "unconnected-(U5-OUT14#-Pad19)") (class "Default")
      (node (ref "U5") (pin "19") (pinfunction "OUT14#_19") (pintype "unspecified+no_connect"))
    )
    (net (code "106") (name "unconnected-(U5-OUT15#-Pad20)") (class "Default")
      (node (ref "U5") (pin "20") (pinfunction "OUT15#_20") (pintype "unspecified+no_connect"))
    )
    (net (code "107") (name "unconnected-(USBC1-SBU1-PadA8)") (class "Default")
      (node (ref "USBC1") (pin "A8") (pinfunction "SBU1_A8") (pintype "unspecified+no_connect"))
    )
    (net (code "108") (name "unconnected-(USBC1-SBU2-PadB8)") (class "Default")
      (node (ref "USBC1") (pin "B8") (pinfunction "SBU2_B8") (pintype "unspecified+no_connect"))
    )
  )
)
